# SCH_Meshtastic-ESP32-C3-super-mini-_-DX-.net
KiCad netlist of a schematic drawn in EasyEDA
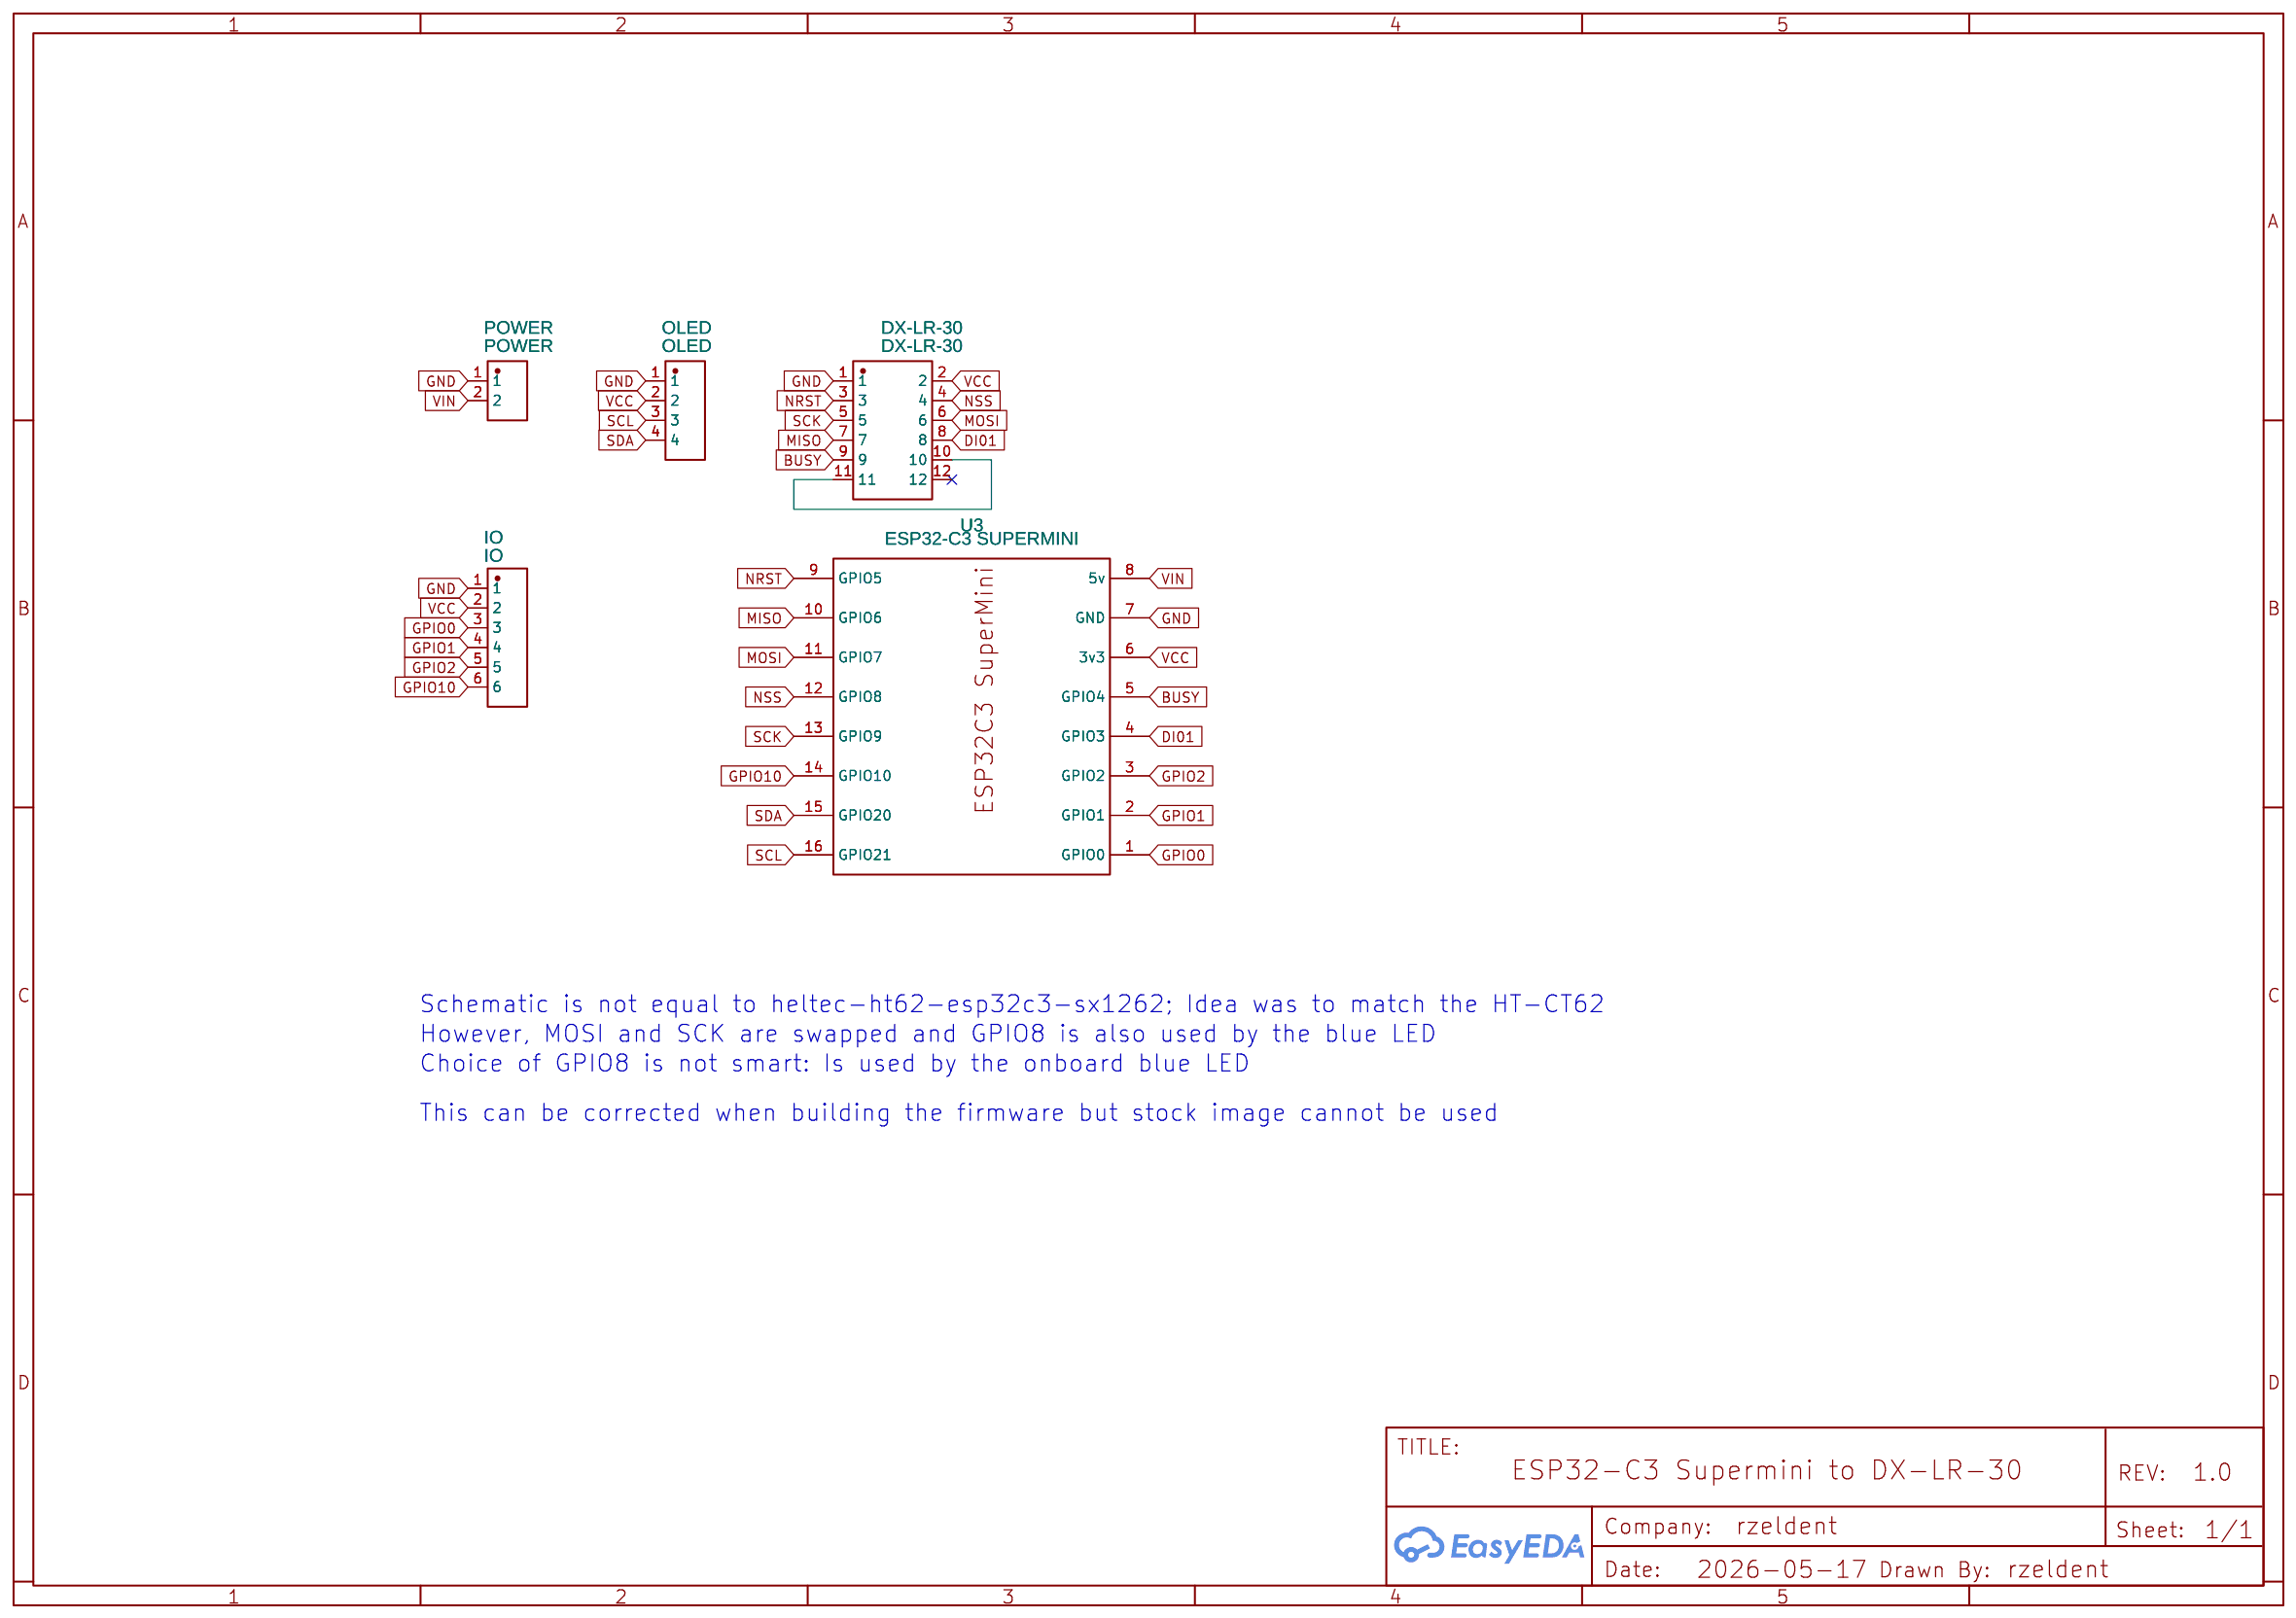
[diagram p0: schematic sheet]

(export (version "E")
  (design (tool "Eeschema 10.0.6"))
  (components
    (comp (ref "DX-LR-30")
      (value "DX-LR-30")
      (fields
        (field (name "Manufacturer Part") "PM2.54-2x6PZZ-H8.5")
        (field (name "Manufacturer") "SHOU HAN(首韩)")
      )
      (libsource (lib "") (part "PM2.54-2X6PZZ-H8.5"))
    )
    (comp (ref "IO")
      (value "IO")
      (fields
        (field (name "Manufacturer Part") "X6511FV-06-C85D32")
        (field (name "Manufacturer") "XKB Connectivity")
      )
      (libsource (lib "") (part "X6511FV-06-C85D32"))
    )
    (comp (ref "OLED")
      (value "OLED")
      (fields (field (name "Manufacturer Part") "PM2.54-1*4") (field (name "Manufacturer") "ZHOURI(洲日)"))
      (libsource (lib "") (part "PM2.54-1*4"))
    )
    (comp (ref "POWER")
      (value "POWER")
      (fields
        (field (name "Manufacturer Part") "XDM254-1-02-Z-8.5-G0")
        (field (name "Manufacturer") "XUNDA(讯答)")
      )
      (libsource (lib "") (part "XDM254-1-02-Z-8.5-G0"))
    )
    (comp (ref "U3") (value "ESP32-C3 SUPERMINI") (libsource (lib "") (part "ESP32C3 SUPERMINI")))
  )
  (nets
    (net (code "1") (name "BUSY") (class "Default")
      (node (ref "DX-LR-30") (pin "9") (pinfunction "9_9") (pintype "unspecified"))
      (node (ref "U3") (pin "5") (pinfunction "GPIO4_5") (pintype "unspecified"))
    )
    (net (code "2") (name "DI01") (class "Default")
      (node (ref "DX-LR-30") (pin "8") (pinfunction "8_8") (pintype "unspecified"))
      (node (ref "U3") (pin "4") (pinfunction "GPIO3_4") (pintype "unspecified"))
    )
    (net (code "3") (name "GND") (class "Default")
      (node (ref "DX-LR-30") (pin "1") (pinfunction "1_1") (pintype "unspecified"))
      (node (ref "IO") (pin "1") (pinfunction "1_1") (pintype "unspecified"))
      (node (ref "OLED") (pin "1") (pinfunction "1_1") (pintype "unspecified"))
      (node (ref "POWER") (pin "1") (pinfunction "1_1") (pintype "unspecified"))
      (node (ref "U3") (pin "7") (pinfunction "GND_7") (pintype "unspecified"))
    )
    (net (code "4") (name "GPIO0") (class "Default")
      (node (ref "IO") (pin "3") (pinfunction "3_3") (pintype "unspecified"))
      (node (ref "U3") (pin "1") (pinfunction "GPIO0_1") (pintype "unspecified"))
    )
    (net (code "5") (name "GPIO1") (class "Default")
      (node (ref "IO") (pin "4") (pinfunction "4_4") (pintype "unspecified"))
      (node (ref "U3") (pin "2") (pinfunction "GPIO1_2") (pintype "unspecified"))
    )
    (net (code "6") (name "GPIO2") (class "Default")
      (node (ref "IO") (pin "5") (pinfunction "5_5") (pintype "unspecified"))
      (node (ref "U3") (pin "3") (pinfunction "GPIO2_3") (pintype "unspecified"))
    )
    (net (code "7") (name "GPIO10") (class "Default")
      (node (ref "IO") (pin "6") (pinfunction "6_6") (pintype "unspecified"))
      (node (ref "U3") (pin "14") (pinfunction "GPIO10_14") (pintype "unspecified"))
    )
    (net (code "8") (name "MISO") (class "Default")
      (node (ref "DX-LR-30") (pin "7") (pinfunction "7_7") (pintype "unspecified"))
      (node (ref "U3") (pin "10") (pinfunction "GPIO6_10") (pintype "unspecified"))
    )
    (net (code "9") (name "MOSI") (class "Default")
      (node (ref "DX-LR-30") (pin "6") (pinfunction "6_6") (pintype "unspecified"))
      (node (ref "U3") (pin "11") (pinfunction "GPIO7_11") (pintype "unspecified"))
    )
    (net (code "10") (name "NRST") (class "Default")
      (node (ref "DX-LR-30") (pin "3") (pinfunction "3_3") (pintype "unspecified"))
      (node (ref "U3") (pin "9") (pinfunction "GPIO5_9") (pintype "unspecified"))
    )
    (net (code "11") (name "NSS") (class "Default")
      (node (ref "DX-LR-30") (pin "4") (pinfunction "4_4") (pintype "unspecified"))
      (node (ref "U3") (pin "12") (pinfunction "GPIO8_12") (pintype "unspecified"))
    )
    (net (code "12") (name "Net-(DX-LR-30-Pad10)") (class "Default")
      (node (ref "DX-LR-30") (pin "10") (pinfunction "10_10") (pintype "unspecified"))
      (node (ref "DX-LR-30") (pin "11") (pinfunction "11_11") (pintype "unspecified"))
    )
    (net (code "13") (name "SCK") (class "Default")
      (node (ref "DX-LR-30") (pin "5") (pinfunction "5_5") (pintype "unspecified"))
      (node (ref "U3") (pin "13") (pinfunction "GPIO9_13") (pintype "unspecified"))
    )
    (net (code "14") (name "SCL") (class "Default")
      (node (ref "OLED") (pin "3") (pinfunction "3_3") (pintype "unspecified"))
      (node (ref "U3") (pin "16") (pinfunction "GPIO21_16") (pintype "unspecified"))
    )
    (net (code "15") (name "SDA") (class "Default")
      (node (ref "OLED") (pin "4") (pinfunction "4_4") (pintype "unspecified"))
      (node (ref "U3") (pin "15") (pinfunction "GPIO20_15") (pintype "unspecified"))
    )
    (net (code "16") (name "VCC") (class "Default")
      (node (ref "DX-LR-30") (pin "2") (pinfunction "2_2") (pintype "unspecified"))
      (node (ref "IO") (pin "2") (pinfunction "2_2") (pintype "unspecified"))
      (node (ref "OLED") (pin "2") (pinfunction "2_2") (pintype "unspecified"))
      (node (ref "U3") (pin "6") (pinfunction "3v3_6") (pintype "unspecified"))
    )
    (net (code "17") (name "VIN") (class "Default")
      (node (ref "POWER") (pin "2") (pinfunction "2_2") (pintype "unspecified"))
      (node (ref "U3") (pin "8") (pinfunction "5v_8") (pintype "unspecified"))
    )
    (net (code "18") (name "unconnected-(DX-LR-30-Pad12)") (class "Default")
      (node (ref "DX-LR-30") (pin "12") (pinfunction "12_12") (pintype "unspecified+no_connect"))
    )
  )
)
